# sensors.net
KiCad netlist of a schematic drawn in Altium Designer
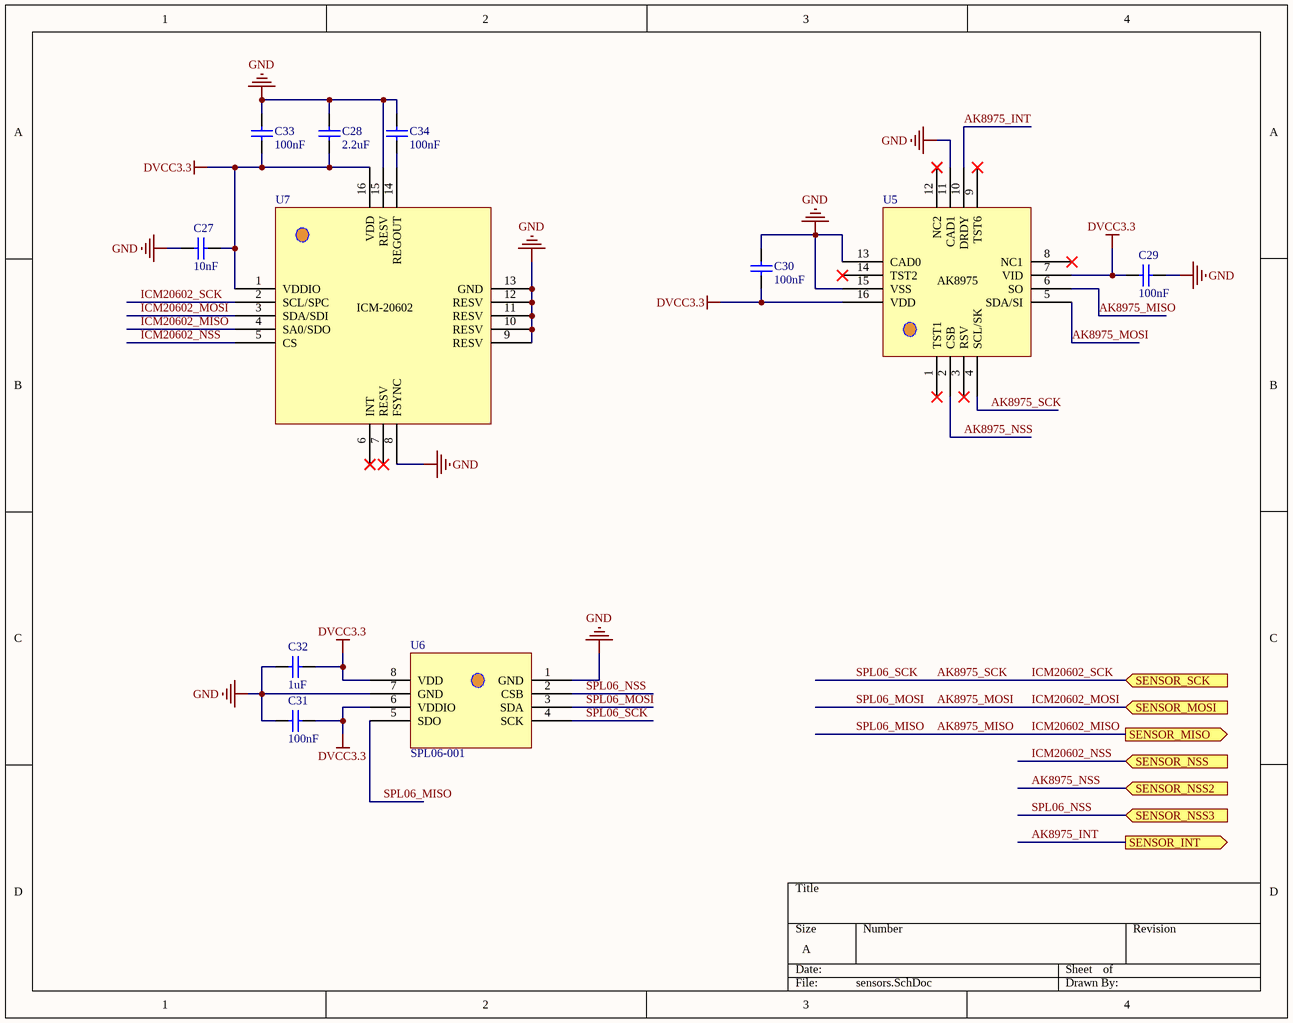
[diagram p0: sensors.SchDoc]

(export (version "E")
  (design (tool "Eeschema 10.0.6"))
  (components
    (comp (ref "C27")
      (value "10nF")
      (footprint "0603_C")
      (description "贴片电容")
      (libsource (lib "Miscellaneous Devices LC") (part "0603 10nF (103) 10% 50V"))
    )
    (comp (ref "C28")
      (value "2.2uF")
      (footprint "0603_C")
      (description "贴片电容")
      (libsource (lib "Miscellaneous Devices LC") (part "0603 2.2uF (225) 10% 16V"))
    )
    (comp (ref "C29")
      (value "100nF")
      (footprint "0603_C")
      (description "贴片电容")
      (libsource (lib "Miscellaneous Devices LC") (part "0603 100nF (104) 10% 50V"))
    )
    (comp (ref "C30")
      (value "100nF")
      (footprint "0603_C")
      (description "贴片电容")
      (libsource (lib "Miscellaneous Devices LC") (part "0603 100nF (104) 10% 50V"))
    )
    (comp (ref "C31")
      (value "100nF")
      (footprint "0603_C")
      (description "贴片电容")
      (libsource (lib "Miscellaneous Devices LC") (part "0603 100nF (104) 10% 50V"))
    )
    (comp (ref "C32")
      (value "1uF")
      (footprint "0603_C")
      (description "贴片电容")
      (libsource (lib "Miscellaneous Devices LC") (part "0603 1uF (105) 10% 50V"))
    )
    (comp (ref "C33")
      (value "100nF")
      (footprint "0603_C")
      (description "贴片电容")
      (libsource (lib "Miscellaneous Devices LC") (part "0603 100nF (104) 10% 50V"))
    )
    (comp (ref "C34")
      (value "100nF")
      (footprint "0603_C")
      (description "贴片电容")
      (libsource (lib "Miscellaneous Devices LC") (part "0603 100nF (104) 10% 50V"))
    )
    (comp (ref "U5")
      (value "AK8975")
      (footprint "AK8975 QFN 16P 400X400X80_HS-17N")
      (libsource (lib "sensors") (part "AK8975"))
    )
    (comp (ref "U6")
      (value "SPL06-001")
      (footprint "spl06-001 LGA 8P 4X2_250X200X100")
      (libsource (lib "sensors") (part "SPL06-001"))
    )
    (comp (ref "U7")
      (value "ICM-20602 6-Axis MEMS")
      (footprint "ICM-20602 LGA")
      (description "High Performance 6-Axis MEMS MotionTracking Device")
      (libsource (lib "sensors") (part "ICM-20602"))
    )
  )
  (nets
    (net (code "1") (name "/AK8975_INT") (class "Default")
      (node (ref "U5") (pin "10") (pinfunction "DRDY_10") (pintype "passive"))
    )
    (net (code "2") (name "/AK8975_MISO") (class "Default")
      (node (ref "U5") (pin "6") (pinfunction "SO_6") (pintype "passive"))
      (node (ref "U6") (pin "5") (pinfunction "SDO_5") (pintype "passive"))
      (node (ref "U7") (pin "4") (pinfunction "SA0/SDO_4") (pintype "passive"))
    )
    (net (code "3") (name "/AK8975_MOSI") (class "Default")
      (node (ref "U5") (pin "5") (pinfunction "SDA/SI_5") (pintype "passive"))
      (node (ref "U6") (pin "3") (pinfunction "SDA_3") (pintype "passive"))
      (node (ref "U7") (pin "3") (pinfunction "SDA/SDI_3") (pintype "passive"))
    )
    (net (code "4") (name "/AK8975_NSS") (class "Default")
      (node (ref "U5") (pin "2") (pinfunction "CSB_2") (pintype "passive"))
    )
    (net (code "5") (name "/AK8975_SCK") (class "Default")
      (node (ref "U5") (pin "4") (pinfunction "SCL/SK_4") (pintype "passive"))
      (node (ref "U6") (pin "4") (pinfunction "SCK_4") (pintype "passive"))
      (node (ref "U7") (pin "2") (pinfunction "SCL/SPC_2") (pintype "passive"))
    )
    (net (code "6") (name "/ICM20602_NSS") (class "Default")
      (node (ref "U7") (pin "5") (pinfunction "CS_5") (pintype "passive"))
    )
    (net (code "7") (name "/SPL06_NSS") (class "Default")
      (node (ref "U6") (pin "2") (pinfunction "CSB_2") (pintype "passive"))
    )
    (net (code "8") (name "DVCC3.3") (class "Default")
      (node (ref "C27") (pin "2") (pinfunction "2_2") (pintype "passive"))
      (node (ref "C28") (pin "1") (pinfunction "1_1") (pintype "passive"))
      (node (ref "C29") (pin "2") (pinfunction "2_2") (pintype "passive"))
      (node (ref "C30") (pin "2") (pinfunction "2_2") (pintype "passive"))
      (node (ref "C31") (pin "1") (pinfunction "1_1") (pintype "passive"))
      (node (ref "C32") (pin "2") (pinfunction "2_2") (pintype "passive"))
      (node (ref "C33") (pin "1") (pinfunction "1_1") (pintype "passive"))
      (node (ref "U5") (pin "16") (pinfunction "VDD_16") (pintype "passive"))
      (node (ref "U5") (pin "7") (pinfunction "VID_7") (pintype "passive"))
      (node (ref "U6") (pin "6") (pinfunction "VDDIO_6") (pintype "passive"))
      (node (ref "U6") (pin "8") (pinfunction "VDD_8") (pintype "passive"))
      (node (ref "U7") (pin "1") (pinfunction "VDDIO_1") (pintype "passive"))
      (node (ref "U7") (pin "16") (pinfunction "VDD_16") (pintype "passive"))
    )
    (net (code "9") (name "GND") (class "Default")
      (node (ref "C27") (pin "1") (pinfunction "1_1") (pintype "passive"))
      (node (ref "C28") (pin "2") (pinfunction "2_2") (pintype "passive"))
      (node (ref "C29") (pin "1") (pinfunction "1_1") (pintype "passive"))
      (node (ref "C30") (pin "1") (pinfunction "1_1") (pintype "passive"))
      (node (ref "C31") (pin "2") (pinfunction "2_2") (pintype "passive"))
      (node (ref "C32") (pin "1") (pinfunction "1_1") (pintype "passive"))
      (node (ref "C33") (pin "2") (pinfunction "2_2") (pintype "passive"))
      (node (ref "C34") (pin "2") (pinfunction "2_2") (pintype "passive"))
      (node (ref "U5") (pin "11") (pinfunction "CAD1_11") (pintype "passive"))
      (node (ref "U5") (pin "13") (pinfunction "CAD0_13") (pintype "passive"))
      (node (ref "U5") (pin "15") (pinfunction "VSS_15") (pintype "passive"))
      (node (ref "U6") (pin "1") (pinfunction "GND_1") (pintype "passive"))
      (node (ref "U6") (pin "7") (pinfunction "GND_7") (pintype "passive"))
      (node (ref "U7") (pin "10") (pinfunction "RESV_10") (pintype "passive"))
      (node (ref "U7") (pin "11") (pinfunction "RESV_11") (pintype "passive"))
      (node (ref "U7") (pin "12") (pinfunction "RESV_12") (pintype "passive"))
      (node (ref "U7") (pin "13") (pinfunction "GND_13") (pintype "passive"))
      (node (ref "U7") (pin "15") (pinfunction "RESV_15") (pintype "passive"))
      (node (ref "U7") (pin "8") (pinfunction "FSYNC_8") (pintype "passive"))
      (node (ref "U7") (pin "9") (pinfunction "RESV_9") (pintype "passive"))
    )
    (net (code "10") (name "Net-(U7-REGOUT)") (class "Default")
      (node (ref "C34") (pin "1") (pinfunction "1_1") (pintype "passive"))
      (node (ref "U7") (pin "14") (pinfunction "REGOUT_14") (pintype "passive"))
    )
    (net (code "11") (name "unconnected-(U5-NC1-Pad8)") (class "Default")
      (node (ref "U5") (pin "8") (pinfunction "NC1_8") (pintype "passive+no_connect"))
    )
    (net (code "12") (name "unconnected-(U5-NC2-Pad12)") (class "Default")
      (node (ref "U5") (pin "12") (pinfunction "NC2_12") (pintype "passive+no_connect"))
    )
    (net (code "13") (name "unconnected-(U5-RSV-Pad3)") (class "Default")
      (node (ref "U5") (pin "3") (pinfunction "RSV_3") (pintype "passive+no_connect"))
    )
    (net (code "14") (name "unconnected-(U5-TST1-Pad1)") (class "Default")
      (node (ref "U5") (pin "1") (pinfunction "TST1_1") (pintype "passive+no_connect"))
    )
    (net (code "15") (name "unconnected-(U5-TST2-Pad14)") (class "Default")
      (node (ref "U5") (pin "14") (pinfunction "TST2_14") (pintype "passive+no_connect"))
    )
    (net (code "16") (name "unconnected-(U5-TST6-Pad9)") (class "Default")
      (node (ref "U5") (pin "9") (pinfunction "TST6_9") (pintype "passive+no_connect"))
    )
    (net (code "17") (name "unconnected-(U7-INT-Pad6)") (class "Default")
      (node (ref "U7") (pin "6") (pinfunction "INT_6") (pintype "passive+no_connect"))
    )
    (net (code "18") (name "unconnected-(U7-RESV-Pad7)") (class "Default")
      (node (ref "U7") (pin "7") (pinfunction "RESV_7") (pintype "passive+no_connect"))
    )
  )
)
